# ATRACK_FACE_V1.net
KiCad netlist of a schematic drawn in Altium Designer
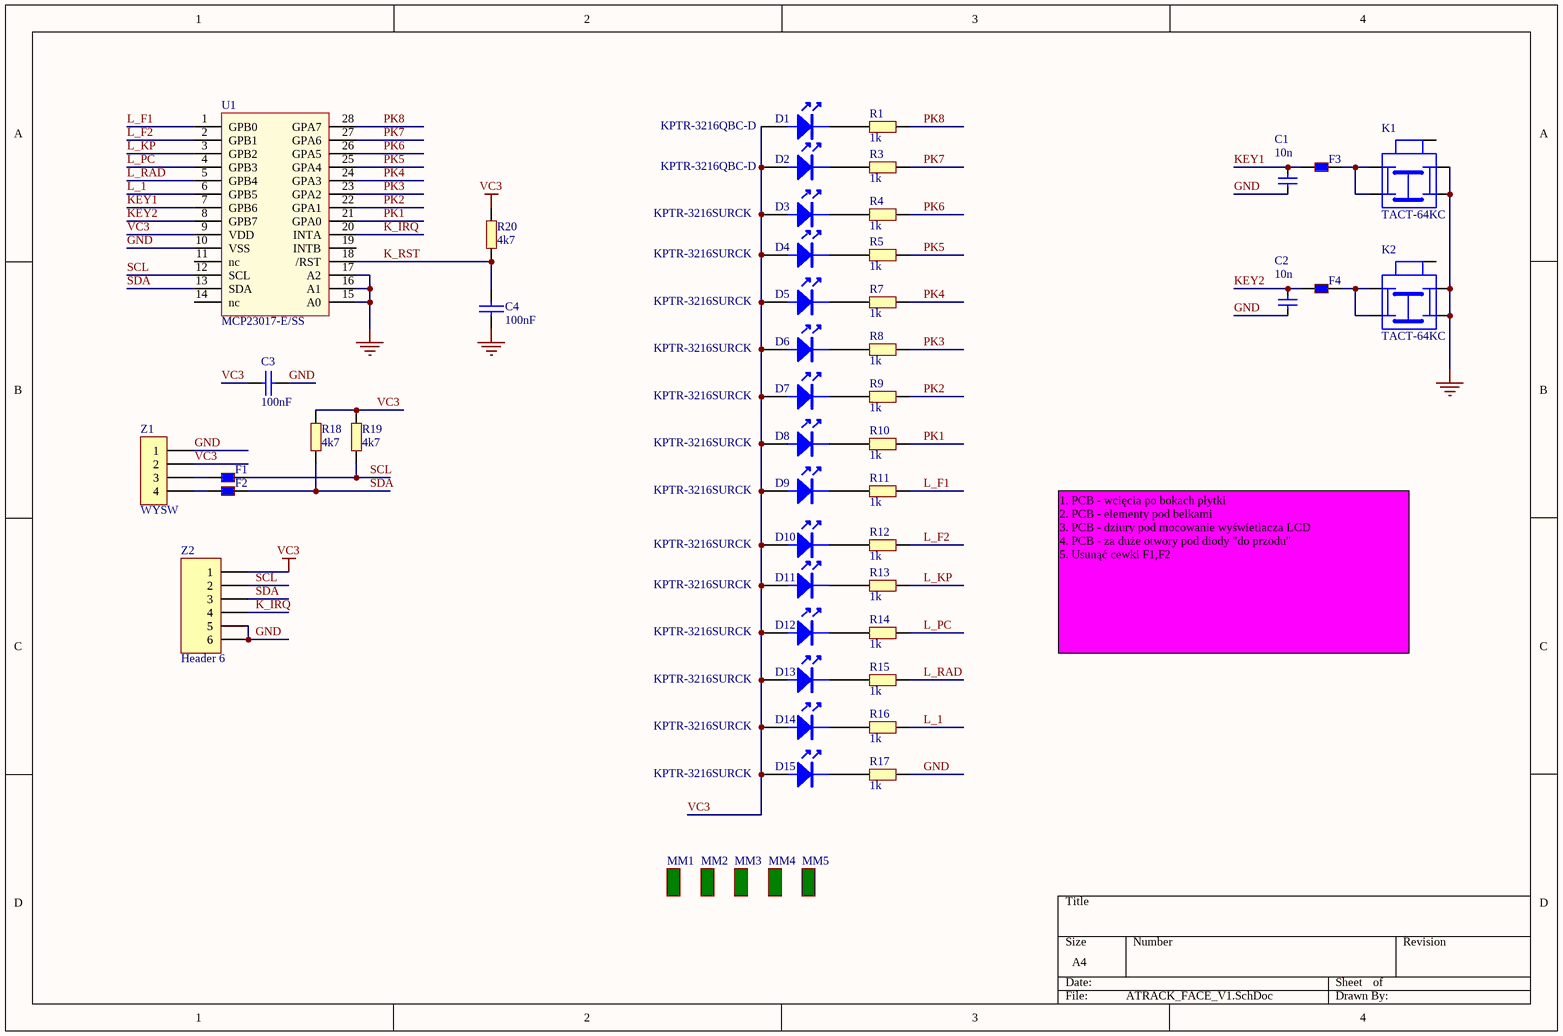
[diagram p0: ATRACK_FACE_V1.SchDoc]

(export (version "E")
  (design (tool "Eeschema 10.0.6"))
  (components
    (comp (ref "C1") (value "10n") (footprint "0805C") (libsource (lib "*") (part "CAP")))
    (comp (ref "C2") (value "10n") (footprint "0805C") (libsource (lib "*") (part "CAP")))
    (comp (ref "C3")
      (value "100nF")
      (footprint "0805C")
      (description "Capacitor")
      (libsource (lib "") (part "CAP_1"))
    )
    (comp (ref "C4")
      (value "100nF")
      (footprint "0805C")
      (description "Capacitor")
      (libsource (lib "") (part "CAP_1"))
    )
    (comp (ref "D1") (value "KPTR-3216QBC-D") (footprint "LED_LAMP_1") (libsource (lib "*") (part "LED")))
    (comp (ref "D2") (value "KPTR-3216QBC-D") (footprint "LED_LAMP_1") (libsource (lib "*") (part "LED")))
    (comp (ref "D3") (value "KPTR-3216SURCK") (footprint "LED_LAMP_1") (libsource (lib "*") (part "LED")))
    (comp (ref "D4")
      (value "KPTR-3216SURCK")
      (footprint "LED_LAMP_1")
      (description "KPTD-3216SGC")
      (libsource (lib "*") (part "LED"))
    )
    (comp (ref "D5")
      (value "KPTR-3216SURCK")
      (footprint "LED_LAMP_1")
      (description "KPTD-3216SGC")
      (libsource (lib "*") (part "LED"))
    )
    (comp (ref "D6")
      (value "KPTR-3216SURCK")
      (footprint "LED_LAMP_1")
      (description "KPTD-3216SGC")
      (libsource (lib "*") (part "LED"))
    )
    (comp (ref "D7")
      (value "KPTR-3216SURCK")
      (footprint "LED_LAMP_1")
      (description "KPTD-3216SGC")
      (libsource (lib "*") (part "LED"))
    )
    (comp (ref "D8")
      (value "KPTR-3216SURCK")
      (footprint "LED_LAMP_1")
      (description "KPTD-3216SGC")
      (libsource (lib "*") (part "LED"))
    )
    (comp (ref "D9")
      (value "KPTR-3216SURCK")
      (footprint "LED_LAMP_1")
      (description "KPTD-3216SGC")
      (libsource (lib "*") (part "LED"))
    )
    (comp (ref "D10") (value "KPTR-3216SURCK") (footprint "LED_LAMP_1") (libsource (lib "*") (part "LED")))
    (comp (ref "D11")
      (value "KPTR-3216SURCK")
      (footprint "LED_LAMP_1")
      (description "KPTD-3216SGC")
      (libsource (lib "*") (part "LED"))
    )
    (comp (ref "D12")
      (value "KPTR-3216SURCK")
      (footprint "LED_LAMP_1")
      (description "KPTD-3216SGC")
      (libsource (lib "*") (part "LED"))
    )
    (comp (ref "D13")
      (value "KPTR-3216SURCK")
      (footprint "LED_LAMP_1")
      (description "KPTD-3216SGC")
      (libsource (lib "*") (part "LED"))
    )
    (comp (ref "D14")
      (value "KPTR-3216SURCK")
      (footprint "LED_LAMP_1")
      (description "KPTD-3216SGC")
      (libsource (lib "*") (part "LED"))
    )
    (comp (ref "D15")
      (value "KPTR-3216SURCK")
      (footprint "LED_LAMP_1")
      (description "KPTD-3216SGC")
      (libsource (lib "*") (part "LED"))
    )
    (comp (ref "F1")
      (value "BLM18BB141SN1D")
      (footprint "0805L")
      (description "Koralik ferrytowy")
      (libsource (lib "*") (part "1812"))
    )
    (comp (ref "F2")
      (value "BLM18BB141SN1D")
      (footprint "0805L")
      (description "Koralik ferrytowy")
      (libsource (lib "*") (part "1812"))
    )
    (comp (ref "F3")
      (value "BLM18BB141SN1D")
      (footprint "0805L")
      (description "Koralik ferrytowy")
      (libsource (lib "*") (part "1812"))
    )
    (comp (ref "F4")
      (value "BLM18BB141SN1D")
      (footprint "0805L")
      (description "Koralik ferrytowy")
      (libsource (lib "*") (part "1812"))
    )
    (comp (ref "K1") (value "TACT-64KC") (footprint "MK_DZ") (libsource (lib "*") (part "KLAW5")))
    (comp (ref "K2") (value "TACT-64KC") (footprint "MK_DZ") (libsource (lib "*") (part "KLAW5")))
    (comp (ref "MM1") (value "~") (footprint "REF_CIR") (libsource (lib "*") (part "MECH")))
    (comp (ref "MM2") (value "~") (footprint "REF_CIR") (libsource (lib "*") (part "MECH")))
    (comp (ref "MM3") (value "~") (footprint "REF_SQR") (libsource (lib "*") (part "MECH")))
    (comp (ref "MM4") (value "~") (footprint "REF_SQR") (libsource (lib "*") (part "MECH")))
    (comp (ref "MM5") (value "~") (footprint "PB_FREE_GRAF") (libsource (lib "*") (part "MECH")))
    (comp (ref "R1") (value "1k") (footprint "0805R") (libsource (lib "*") (part "RES3")))
    (comp (ref "R3") (value "1k") (footprint "0805R") (libsource (lib "*") (part "RES3")))
    (comp (ref "R4") (value "1k") (footprint "0805R") (libsource (lib "*") (part "RES3")))
    (comp (ref "R5") (value "1k") (footprint "0805R") (libsource (lib "*") (part "RES3")))
    (comp (ref "R7") (value "1k") (footprint "0805R") (libsource (lib "*") (part "RES3")))
    (comp (ref "R8") (value "1k") (footprint "0805R") (libsource (lib "*") (part "RES3")))
    (comp (ref "R9") (value "1k") (footprint "0805R") (libsource (lib "*") (part "RES3")))
    (comp (ref "R10") (value "1k") (footprint "0805R") (libsource (lib "*") (part "RES3")))
    (comp (ref "R11") (value "1k") (footprint "0805R") (libsource (lib "*") (part "RES3")))
    (comp (ref "R12") (value "1k") (footprint "0805R") (libsource (lib "*") (part "RES3")))
    (comp (ref "R13") (value "1k") (footprint "0805R") (libsource (lib "*") (part "RES3")))
    (comp (ref "R14") (value "1k") (footprint "0805R") (libsource (lib "*") (part "RES3")))
    (comp (ref "R15") (value "1k") (footprint "0805R") (libsource (lib "*") (part "RES3")))
    (comp (ref "R16") (value "1k") (footprint "0805R") (libsource (lib "*") (part "RES3")))
    (comp (ref "R17") (value "1k") (footprint "0805R") (libsource (lib "*") (part "RES3")))
    (comp (ref "R18") (value "4k7") (footprint "0805R") (libsource (lib "") (part "RES3_1")))
    (comp (ref "R19") (value "4k7") (footprint "0805R") (libsource (lib "") (part "RES3_1")))
    (comp (ref "R20") (value "4k7") (footprint "0805R") (libsource (lib "") (part "RES3_1")))
    (comp (ref "U1")
      (value "MCP23017-E/SS")
      (footprint "SSOP28")
      (libsource (lib "GkSchlib") (part "MCP23017_SSOP28"))
    )
    (comp (ref "Z1")
      (value "WYSW")
      (footprint "SSD1306_KW")
      (description "Connector")
      (libsource (lib "*") (part "CON4"))
    )
    (comp (ref "Z2")
      (value "Header 6")
      (footprint "UMATCH-6SMD")
      (description "Micro Match 6")
      (fields (field (name "PUBLISHER") "Altium Limited"))
      (libsource (lib "Miscellaneous Connectors") (part "Header 6"))
    )
  )
  (nets
    (net (code "1") (name "/KEY1") (class "Default")
      (node (ref "C1") (pin "1") (pintype "passive"))
      (node (ref "F3") (pin "1") (pintype "passive"))
      (node (ref "U1") (pin "7") (pinfunction "GPB6_7") (pintype "passive"))
    )
    (net (code "2") (name "/KEY2") (class "Default")
      (node (ref "C2") (pin "1") (pintype "passive"))
      (node (ref "F4") (pin "1") (pintype "passive"))
      (node (ref "U1") (pin "8") (pinfunction "GPB7_8") (pintype "passive"))
    )
    (net (code "3") (name "/K_IRQ") (class "Default")
      (node (ref "U1") (pin "20") (pinfunction "INTA_20") (pintype "passive"))
      (node (ref "Z2") (pin "4") (pinfunction "4_4") (pintype "passive"))
    )
    (net (code "4") (name "/K_RST") (class "Default")
      (node (ref "C4") (pin "1") (pinfunction "1_1") (pintype "passive"))
      (node (ref "R20") (pin "2") (pintype "passive"))
      (node (ref "U1") (pin "18") (pinfunction "/RST_18") (pintype "passive"))
    )
    (net (code "5") (name "/L_1") (class "Default")
      (node (ref "R16") (pin "1") (pintype "passive"))
      (node (ref "U1") (pin "6") (pinfunction "GPB5_6") (pintype "passive"))
    )
    (net (code "6") (name "/L_F1") (class "Default")
      (node (ref "R11") (pin "1") (pintype "passive"))
      (node (ref "U1") (pin "1") (pinfunction "GPB0_1") (pintype "passive"))
    )
    (net (code "7") (name "/L_F2") (class "Default")
      (node (ref "R12") (pin "1") (pintype "passive"))
      (node (ref "U1") (pin "2") (pinfunction "GPB1_2") (pintype "passive"))
    )
    (net (code "8") (name "/L_KP") (class "Default")
      (node (ref "R13") (pin "1") (pintype "passive"))
      (node (ref "U1") (pin "3") (pinfunction "GPB2_3") (pintype "passive"))
    )
    (net (code "9") (name "/L_PC") (class "Default")
      (node (ref "R14") (pin "1") (pintype "passive"))
      (node (ref "U1") (pin "4") (pinfunction "GPB3_4") (pintype "passive"))
    )
    (net (code "10") (name "/L_RAD") (class "Default")
      (node (ref "R15") (pin "1") (pintype "passive"))
      (node (ref "U1") (pin "5") (pinfunction "GPB4_5") (pintype "passive"))
    )
    (net (code "11") (name "/PK1") (class "Default")
      (node (ref "R10") (pin "1") (pintype "passive"))
      (node (ref "U1") (pin "21") (pinfunction "GPA0_21") (pintype "passive"))
    )
    (net (code "12") (name "/PK2") (class "Default")
      (node (ref "R9") (pin "1") (pintype "passive"))
      (node (ref "U1") (pin "22") (pinfunction "GPA1_22") (pintype "passive"))
    )
    (net (code "13") (name "/PK3") (class "Default")
      (node (ref "R8") (pin "1") (pintype "passive"))
      (node (ref "U1") (pin "23") (pinfunction "GPA2_23") (pintype "passive"))
    )
    (net (code "14") (name "/PK4") (class "Default")
      (node (ref "R7") (pin "1") (pintype "passive"))
      (node (ref "U1") (pin "24") (pinfunction "GPA3_24") (pintype "passive"))
    )
    (net (code "15") (name "/PK5") (class "Default")
      (node (ref "R5") (pin "1") (pintype "passive"))
      (node (ref "U1") (pin "25") (pinfunction "GPA4_25") (pintype "passive"))
    )
    (net (code "16") (name "/PK6") (class "Default")
      (node (ref "R4") (pin "1") (pintype "passive"))
      (node (ref "U1") (pin "26") (pinfunction "GPA5_26") (pintype "passive"))
    )
    (net (code "17") (name "/PK7") (class "Default")
      (node (ref "R3") (pin "1") (pintype "passive"))
      (node (ref "U1") (pin "27") (pinfunction "GPA6_27") (pintype "passive"))
    )
    (net (code "18") (name "/PK8") (class "Default")
      (node (ref "R1") (pin "1") (pintype "passive"))
      (node (ref "U1") (pin "28") (pinfunction "GPA7_28") (pintype "passive"))
    )
    (net (code "19") (name "/SCL") (class "Default")
      (node (ref "F1") (pin "2") (pintype "passive"))
      (node (ref "R19") (pin "2") (pintype "passive"))
      (node (ref "U1") (pin "12") (pinfunction "SCL_12") (pintype "passive"))
      (node (ref "Z2") (pin "2") (pinfunction "2_2") (pintype "passive"))
    )
    (net (code "20") (name "/SDA") (class "Default")
      (node (ref "F2") (pin "2") (pintype "passive"))
      (node (ref "R18") (pin "2") (pintype "passive"))
      (node (ref "U1") (pin "13") (pinfunction "SDA_13") (pintype "passive"))
      (node (ref "Z2") (pin "3") (pinfunction "3_3") (pintype "passive"))
    )
    (net (code "21") (name "GND") (class "Default")
      (node (ref "C1") (pin "2") (pintype "passive"))
      (node (ref "C2") (pin "2") (pintype "passive"))
      (node (ref "C3") (pin "2") (pinfunction "2_2") (pintype "passive"))
      (node (ref "C4") (pin "2") (pinfunction "2_2") (pintype "passive"))
      (node (ref "K1") (pin "3") (pinfunction "3_3") (pintype "passive"))
      (node (ref "K1") (pin "4") (pinfunction "4_4") (pintype "passive"))
      (node (ref "K2") (pin "3") (pinfunction "3_3") (pintype "passive"))
      (node (ref "K2") (pin "4") (pinfunction "4_4") (pintype "passive"))
      (node (ref "R17") (pin "1") (pintype "passive"))
      (node (ref "U1") (pin "10") (pinfunction "VSS_10") (pintype "passive"))
      (node (ref "U1") (pin "15") (pinfunction "A0_15") (pintype "passive"))
      (node (ref "U1") (pin "16") (pinfunction "A1_16") (pintype "passive"))
      (node (ref "U1") (pin "17") (pinfunction "A2_17") (pintype "passive"))
      (node (ref "Z1") (pin "1") (pinfunction "1_1") (pintype "passive"))
      (node (ref "Z2") (pin "5") (pinfunction "5_5") (pintype "passive"))
      (node (ref "Z2") (pin "6") (pinfunction "6_6") (pintype "passive"))
    )
    (net (code "22") (name "Net-(D1-2)") (class "Default")
      (node (ref "D1") (pin "K") (pinfunction "2_K") (pintype "passive"))
      (node (ref "R1") (pin "2") (pintype "passive"))
    )
    (net (code "23") (name "Net-(D2-2)") (class "Default")
      (node (ref "D2") (pin "K") (pinfunction "2_K") (pintype "passive"))
      (node (ref "R3") (pin "2") (pintype "passive"))
    )
    (net (code "24") (name "Net-(D3-2)") (class "Default")
      (node (ref "D3") (pin "K") (pinfunction "2_K") (pintype "passive"))
      (node (ref "R4") (pin "2") (pintype "passive"))
    )
    (net (code "25") (name "Net-(D4-2)") (class "Default")
      (node (ref "D4") (pin "K") (pinfunction "2_K") (pintype "passive"))
      (node (ref "R5") (pin "2") (pintype "passive"))
    )
    (net (code "26") (name "Net-(D5-2)") (class "Default")
      (node (ref "D5") (pin "K") (pinfunction "2_K") (pintype "passive"))
      (node (ref "R7") (pin "2") (pintype "passive"))
    )
    (net (code "27") (name "Net-(D6-2)") (class "Default")
      (node (ref "D6") (pin "K") (pinfunction "2_K") (pintype "passive"))
      (node (ref "R8") (pin "2") (pintype "passive"))
    )
    (net (code "28") (name "Net-(D7-2)") (class "Default")
      (node (ref "D7") (pin "K") (pinfunction "2_K") (pintype "passive"))
      (node (ref "R9") (pin "2") (pintype "passive"))
    )
    (net (code "29") (name "Net-(D8-2)") (class "Default")
      (node (ref "D8") (pin "K") (pinfunction "2_K") (pintype "passive"))
      (node (ref "R10") (pin "2") (pintype "passive"))
    )
    (net (code "30") (name "Net-(D9-2)") (class "Default")
      (node (ref "D9") (pin "K") (pinfunction "2_K") (pintype "passive"))
      (node (ref "R11") (pin "2") (pintype "passive"))
    )
    (net (code "31") (name "Net-(D10-2)") (class "Default")
      (node (ref "D10") (pin "K") (pinfunction "2_K") (pintype "passive"))
      (node (ref "R12") (pin "2") (pintype "passive"))
    )
    (net (code "32") (name "Net-(D11-2)") (class "Default")
      (node (ref "D11") (pin "K") (pinfunction "2_K") (pintype "passive"))
      (node (ref "R13") (pin "2") (pintype "passive"))
    )
    (net (code "33") (name "Net-(D12-2)") (class "Default")
      (node (ref "D12") (pin "K") (pinfunction "2_K") (pintype "passive"))
      (node (ref "R14") (pin "2") (pintype "passive"))
    )
    (net (code "34") (name "Net-(D13-2)") (class "Default")
      (node (ref "D13") (pin "K") (pinfunction "2_K") (pintype "passive"))
      (node (ref "R15") (pin "2") (pintype "passive"))
    )
    (net (code "35") (name "Net-(D14-2)") (class "Default")
      (node (ref "D14") (pin "K") (pinfunction "2_K") (pintype "passive"))
      (node (ref "R16") (pin "2") (pintype "passive"))
    )
    (net (code "36") (name "Net-(D15-2)") (class "Default")
      (node (ref "D15") (pin "K") (pinfunction "2_K") (pintype "passive"))
      (node (ref "R17") (pin "2") (pintype "passive"))
    )
    (net (code "37") (name "Net-(F1-Pad1)") (class "Default")
      (node (ref "F1") (pin "1") (pintype "passive"))
      (node (ref "Z1") (pin "3") (pinfunction "3_3") (pintype "passive"))
    )
    (net (code "38") (name "Net-(F2-Pad1)") (class "Default")
      (node (ref "F2") (pin "1") (pintype "passive"))
      (node (ref "Z1") (pin "4") (pinfunction "4_4") (pintype "passive"))
    )
    (net (code "39") (name "Net-(F3-Pad2)") (class "Default")
      (node (ref "F3") (pin "2") (pintype "passive"))
      (node (ref "K1") (pin "1") (pinfunction "1_1") (pintype "passive"))
      (node (ref "K1") (pin "2") (pinfunction "2_2") (pintype "passive"))
    )
    (net (code "40") (name "Net-(F4-Pad2)") (class "Default")
      (node (ref "F4") (pin "2") (pintype "passive"))
      (node (ref "K2") (pin "1") (pinfunction "1_1") (pintype "passive"))
      (node (ref "K2") (pin "2") (pinfunction "2_2") (pintype "passive"))
    )
    (net (code "41") (name "VC3") (class "Default")
      (node (ref "C3") (pin "1") (pinfunction "1_1") (pintype "passive"))
      (node (ref "D1") (pin "A") (pinfunction "1_A") (pintype "passive"))
      (node (ref "D10") (pin "A") (pinfunction "1_A") (pintype "passive"))
      (node (ref "D11") (pin "A") (pinfunction "1_A") (pintype "passive"))
      (node (ref "D12") (pin "A") (pinfunction "1_A") (pintype "passive"))
      (node (ref "D13") (pin "A") (pinfunction "1_A") (pintype "passive"))
      (node (ref "D14") (pin "A") (pinfunction "1_A") (pintype "passive"))
      (node (ref "D15") (pin "A") (pinfunction "1_A") (pintype "passive"))
      (node (ref "D2") (pin "A") (pinfunction "1_A") (pintype "passive"))
      (node (ref "D3") (pin "A") (pinfunction "1_A") (pintype "passive"))
      (node (ref "D4") (pin "A") (pinfunction "1_A") (pintype "passive"))
      (node (ref "D5") (pin "A") (pinfunction "1_A") (pintype "passive"))
      (node (ref "D6") (pin "A") (pinfunction "1_A") (pintype "passive"))
      (node (ref "D7") (pin "A") (pinfunction "1_A") (pintype "passive"))
      (node (ref "D8") (pin "A") (pinfunction "1_A") (pintype "passive"))
      (node (ref "D9") (pin "A") (pinfunction "1_A") (pintype "passive"))
      (node (ref "R18") (pin "1") (pintype "passive"))
      (node (ref "R19") (pin "1") (pintype "passive"))
      (node (ref "R20") (pin "1") (pintype "passive"))
      (node (ref "U1") (pin "9") (pinfunction "VDD_9") (pintype "passive"))
      (node (ref "Z1") (pin "2") (pinfunction "2_2") (pintype "passive"))
      (node (ref "Z2") (pin "1") (pinfunction "1_1") (pintype "passive"))
    )
    (net (code "42") (name "unconnected-(K1-Pad5)") (class "Default")
      (node (ref "K1") (pin "5") (pinfunction "5_5") (pintype "passive"))
    )
    (net (code "43") (name "unconnected-(K2-Pad5)") (class "Default")
      (node (ref "K2") (pin "5") (pinfunction "5_5") (pintype "passive"))
    )
    (net (code "44") (name "unconnected-(U1-INTB-Pad19)") (class "Default")
      (node (ref "U1") (pin "19") (pinfunction "INTB_19") (pintype "passive"))
    )
    (net (code "45") (name "unconnected-(U1-nc-Pad11)") (class "Default")
      (node (ref "U1") (pin "11") (pinfunction "nc_11") (pintype "passive"))
    )
    (net (code "46") (name "unconnected-(U1-nc-Pad14)") (class "Default")
      (node (ref "U1") (pin "14") (pinfunction "nc_14") (pintype "passive"))
    )
  )
)
